# GPU_8_Bit_Logic_Template.net
KiCad netlist of a schematic drawn in EAGLE
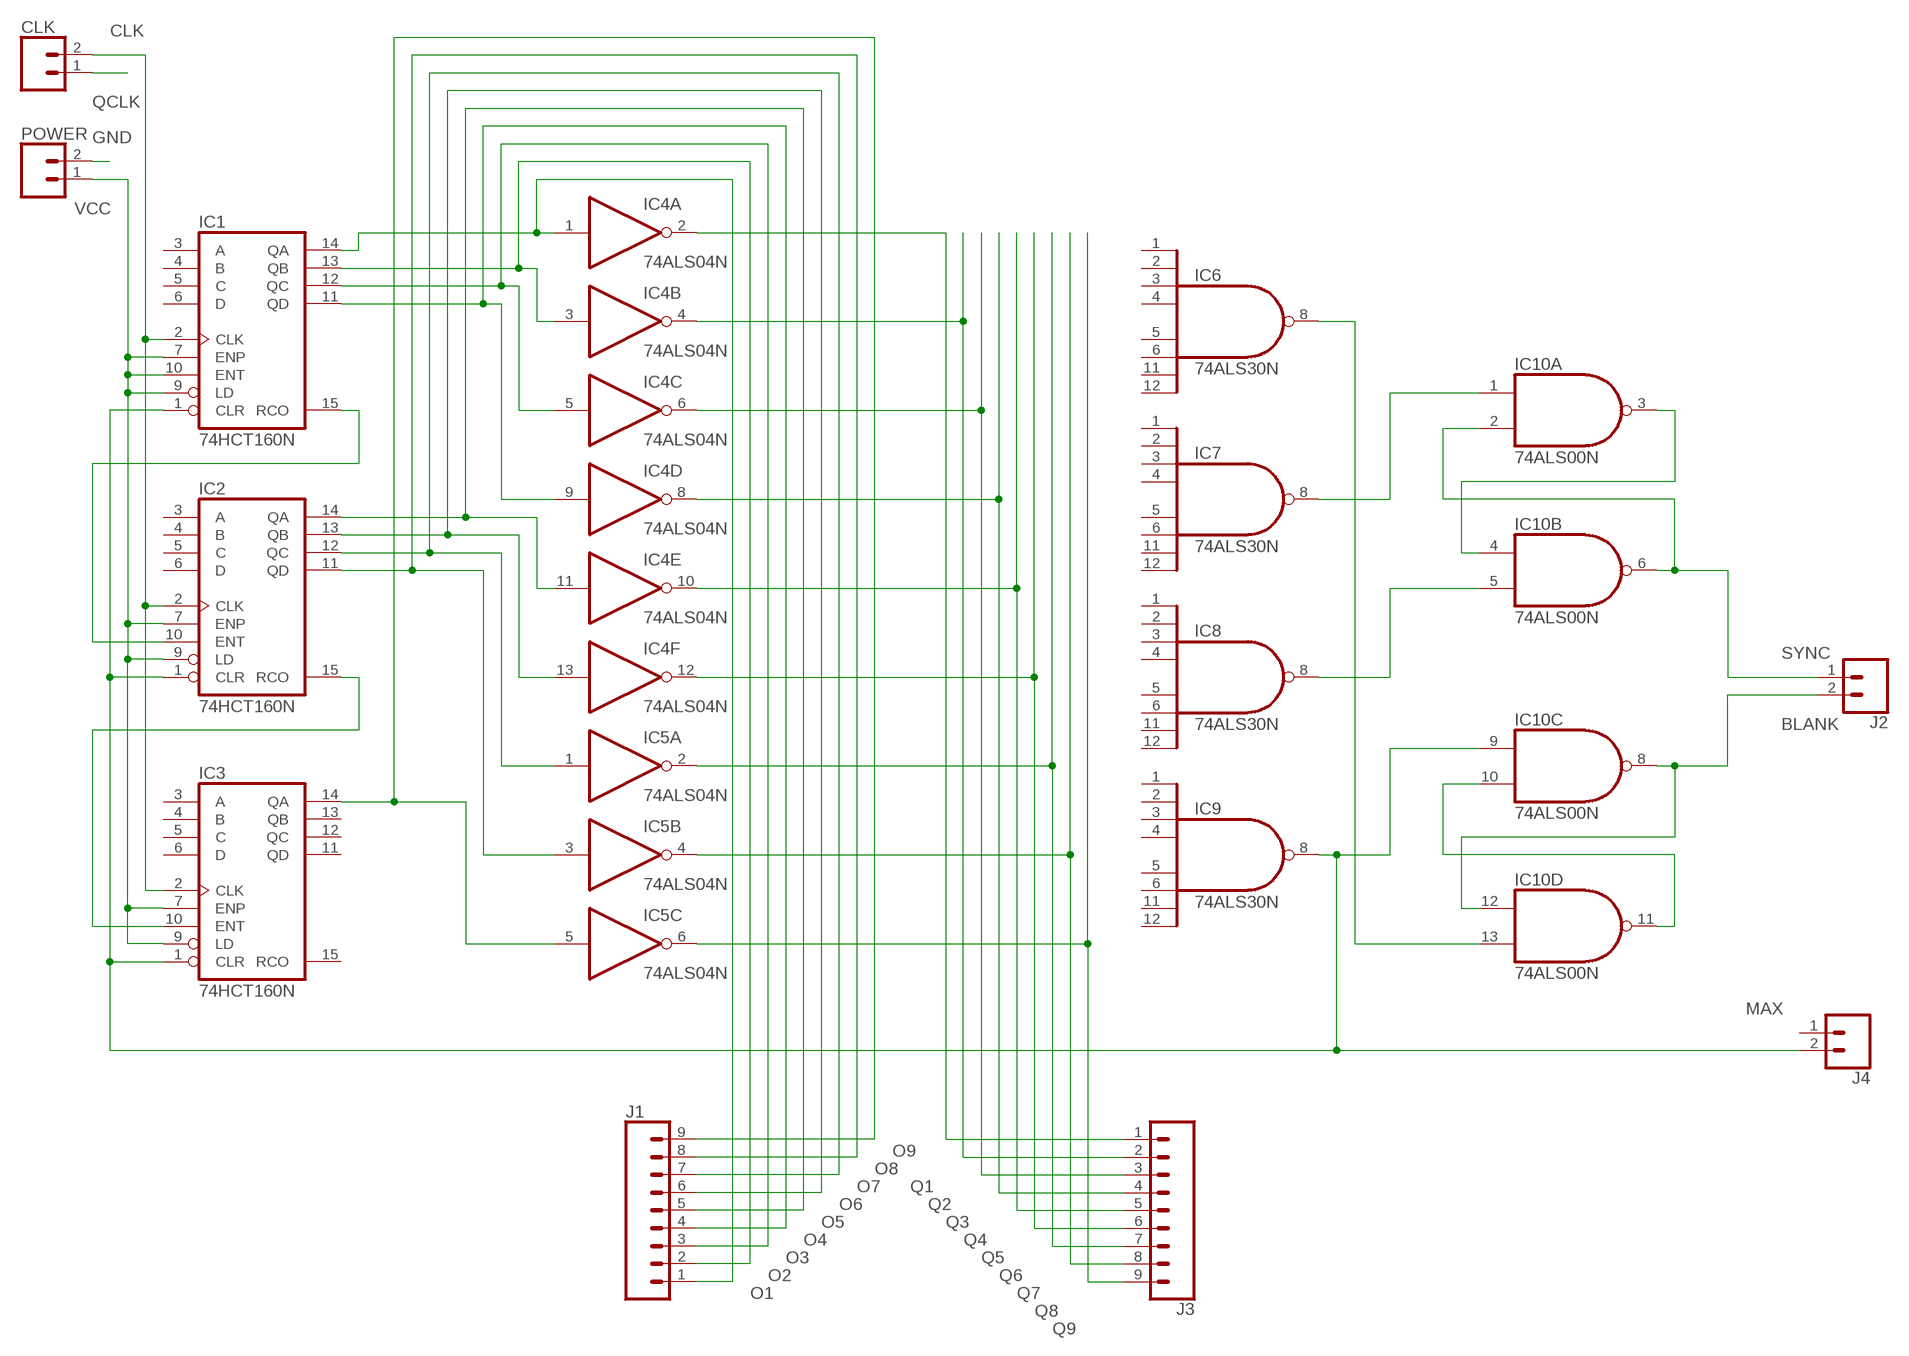
[diagram p0: schematic, sheet 1]

(export (version "E")
  (design (tool "Eeschema 10.0.6"))
  (components
    (comp (ref "CLK")
      (value "CONN_02POGO_PIN_HOLES_ONLY")
      (footprint "eagle-import:1X02_PP_HOLES_ONLY")
      (libsource (lib "eagle-import") (part "CONN_02POGO_PIN_HOLES_ONLY"))
    )
    (comp (ref "IC1")
      (value "74HCT160N")
      (footprint "eagle-import:DIL16")
      (libsource (lib "eagle-import") (part "74160NHCT"))
    )
    (comp (ref "IC2")
      (value "74HCT160N")
      (footprint "eagle-import:DIL16")
      (libsource (lib "eagle-import") (part "74160NHCT"))
    )
    (comp (ref "IC3")
      (value "74HCT160N")
      (footprint "eagle-import:DIL16")
      (libsource (lib "eagle-import") (part "74160NHCT"))
    )
    (comp (ref "IC4")
      (value "74ALS04N")
      (footprint "eagle-import:DIL14")
      (libsource (lib "eagle-import") (part "7404NALS"))
    )
    (comp (ref "IC5")
      (value "74ALS04N")
      (footprint "eagle-import:DIL14")
      (libsource (lib "eagle-import") (part "7404NALS"))
    )
    (comp (ref "IC6")
      (value "74ALS30N")
      (footprint "eagle-import:DIL14")
      (libsource (lib "eagle-import") (part "7430NALS"))
    )
    (comp (ref "IC7")
      (value "74ALS30N")
      (footprint "eagle-import:DIL14")
      (libsource (lib "eagle-import") (part "7430NALS"))
    )
    (comp (ref "IC8")
      (value "74ALS30N")
      (footprint "eagle-import:DIL14")
      (libsource (lib "eagle-import") (part "7430NALS"))
    )
    (comp (ref "IC9")
      (value "74ALS30N")
      (footprint "eagle-import:DIL14")
      (libsource (lib "eagle-import") (part "7430NALS"))
    )
    (comp (ref "IC10")
      (value "74ALS00N")
      (footprint "eagle-import:DIL14")
      (libsource (lib "eagle-import") (part "7400NALS"))
    )
    (comp (ref "J1")
      (value "CONN_09")
      (footprint "eagle-import:1X09")
      (libsource (lib "eagle-import") (part "CONN_09"))
    )
    (comp (ref "J2")
      (value "CONN_02POGO_PIN_HOLES_ONLY")
      (footprint "eagle-import:1X02_PP_HOLES_ONLY")
      (libsource (lib "eagle-import") (part "CONN_02POGO_PIN_HOLES_ONLY"))
    )
    (comp (ref "J3")
      (value "CONN_09")
      (footprint "eagle-import:1X09")
      (libsource (lib "eagle-import") (part "CONN_09"))
    )
    (comp (ref "J4")
      (value "CONN_02POGO_PIN_HOLES_ONLY")
      (footprint "eagle-import:1X02_PP_HOLES_ONLY")
      (libsource (lib "eagle-import") (part "CONN_02POGO_PIN_HOLES_ONLY"))
    )
    (comp (ref "POWER")
      (value "CONN_02POGO_PIN_HOLES_ONLY")
      (footprint "eagle-import:1X02_PP_HOLES_ONLY")
      (libsource (lib "eagle-import") (part "CONN_02POGO_PIN_HOLES_ONLY"))
    )
  )
  (nets
    (net (code "1") (name "/BLANK") (class "Default")
      (node (ref "IC10") (pin "12") (pinfunction "I0_12") (pintype "input"))
      (node (ref "IC10") (pin "8") (pinfunction "O_8") (pintype "output"))
      (node (ref "J2") (pin "2") (pinfunction "2_2") (pintype "passive"))
    )
    (net (code "2") (name "/CLK") (class "Default")
      (node (ref "CLK") (pin "2") (pinfunction "2_2") (pintype "passive"))
      (node (ref "IC1") (pin "2") (pinfunction "CLK_2") (pintype "input"))
      (node (ref "IC2") (pin "2") (pinfunction "CLK_2") (pintype "input"))
      (node (ref "IC3") (pin "2") (pinfunction "CLK_2") (pintype "input"))
    )
    (net (code "3") (name "/GND") (class "Default")
      (node (ref "POWER") (pin "2") (pinfunction "2_2") (pintype "passive"))
    )
    (net (code "4") (name "/MAX") (class "Default")
      (node (ref "IC1") (pin "1") (pinfunction "CLR_1") (pintype "input"))
      (node (ref "IC10") (pin "9") (pinfunction "I0_9") (pintype "input"))
      (node (ref "IC2") (pin "1") (pinfunction "CLR_1") (pintype "input"))
      (node (ref "IC3") (pin "1") (pinfunction "CLR_1") (pintype "input"))
      (node (ref "IC9") (pin "8") (pinfunction "O_8") (pintype "output"))
      (node (ref "J4") (pin "2") (pinfunction "2_2") (pintype "passive"))
    )
    (net (code "5") (name "/O1") (class "Default")
      (node (ref "IC1") (pin "14") (pinfunction "QA_14") (pintype "output"))
      (node (ref "IC4") (pin "1") (pinfunction "I_1") (pintype "input"))
      (node (ref "J1") (pin "1") (pinfunction "1_1") (pintype "passive"))
    )
    (net (code "6") (name "/O2") (class "Default")
      (node (ref "IC1") (pin "13") (pinfunction "QB_13") (pintype "output"))
      (node (ref "IC4") (pin "3") (pinfunction "I_3") (pintype "input"))
      (node (ref "J1") (pin "2") (pinfunction "2_2") (pintype "passive"))
    )
    (net (code "7") (name "/O3") (class "Default")
      (node (ref "IC1") (pin "12") (pinfunction "QC_12") (pintype "output"))
      (node (ref "IC4") (pin "5") (pinfunction "I_5") (pintype "input"))
      (node (ref "J1") (pin "3") (pinfunction "3_3") (pintype "passive"))
    )
    (net (code "8") (name "/O4") (class "Default")
      (node (ref "IC1") (pin "11") (pinfunction "QD_11") (pintype "output"))
      (node (ref "IC4") (pin "9") (pinfunction "I_9") (pintype "input"))
      (node (ref "J1") (pin "4") (pinfunction "4_4") (pintype "passive"))
    )
    (net (code "9") (name "/O5") (class "Default")
      (node (ref "IC2") (pin "14") (pinfunction "QA_14") (pintype "output"))
      (node (ref "IC4") (pin "11") (pinfunction "I_11") (pintype "input"))
      (node (ref "J1") (pin "5") (pinfunction "5_5") (pintype "passive"))
    )
    (net (code "10") (name "/O6") (class "Default")
      (node (ref "IC2") (pin "13") (pinfunction "QB_13") (pintype "output"))
      (node (ref "IC4") (pin "13") (pinfunction "I_13") (pintype "input"))
      (node (ref "J1") (pin "6") (pinfunction "6_6") (pintype "passive"))
    )
    (net (code "11") (name "/O7") (class "Default")
      (node (ref "IC2") (pin "12") (pinfunction "QC_12") (pintype "output"))
      (node (ref "IC5") (pin "1") (pinfunction "I_1") (pintype "input"))
      (node (ref "J1") (pin "7") (pinfunction "7_7") (pintype "passive"))
    )
    (net (code "12") (name "/O8") (class "Default")
      (node (ref "IC2") (pin "11") (pinfunction "QD_11") (pintype "output"))
      (node (ref "IC5") (pin "3") (pinfunction "I_3") (pintype "input"))
      (node (ref "J1") (pin "8") (pinfunction "8_8") (pintype "passive"))
    )
    (net (code "13") (name "/O9") (class "Default")
      (node (ref "IC3") (pin "14") (pinfunction "QA_14") (pintype "output"))
      (node (ref "IC5") (pin "5") (pinfunction "I_5") (pintype "input"))
      (node (ref "J1") (pin "9") (pinfunction "9_9") (pintype "passive"))
    )
    (net (code "14") (name "/Q1") (class "Default")
      (node (ref "IC4") (pin "2") (pinfunction "O_2") (pintype "output"))
      (node (ref "J3") (pin "1") (pinfunction "1_1") (pintype "passive"))
    )
    (net (code "15") (name "/Q2") (class "Default")
      (node (ref "IC4") (pin "4") (pinfunction "O_4") (pintype "output"))
      (node (ref "J3") (pin "2") (pinfunction "2_2") (pintype "passive"))
    )
    (net (code "16") (name "/Q3") (class "Default")
      (node (ref "IC4") (pin "6") (pinfunction "O_6") (pintype "output"))
      (node (ref "J3") (pin "3") (pinfunction "3_3") (pintype "passive"))
    )
    (net (code "17") (name "/Q4") (class "Default")
      (node (ref "IC4") (pin "8") (pinfunction "O_8") (pintype "output"))
      (node (ref "J3") (pin "4") (pinfunction "4_4") (pintype "passive"))
    )
    (net (code "18") (name "/Q5") (class "Default")
      (node (ref "IC4") (pin "10") (pinfunction "O_10") (pintype "output"))
      (node (ref "J3") (pin "5") (pinfunction "5_5") (pintype "passive"))
    )
    (net (code "19") (name "/Q6") (class "Default")
      (node (ref "IC4") (pin "12") (pinfunction "O_12") (pintype "output"))
      (node (ref "J3") (pin "6") (pinfunction "6_6") (pintype "passive"))
    )
    (net (code "20") (name "/Q7") (class "Default")
      (node (ref "IC5") (pin "2") (pinfunction "O_2") (pintype "output"))
      (node (ref "J3") (pin "7") (pinfunction "7_7") (pintype "passive"))
    )
    (net (code "21") (name "/Q8") (class "Default")
      (node (ref "IC5") (pin "4") (pinfunction "O_4") (pintype "output"))
      (node (ref "J3") (pin "8") (pinfunction "8_8") (pintype "passive"))
    )
    (net (code "22") (name "/Q9") (class "Default")
      (node (ref "IC5") (pin "6") (pinfunction "O_6") (pintype "output"))
      (node (ref "J3") (pin "9") (pinfunction "9_9") (pintype "passive"))
    )
    (net (code "23") (name "/QCLK") (class "Default")
      (node (ref "CLK") (pin "1") (pinfunction "1_1") (pintype "passive"))
    )
    (net (code "24") (name "/SYNC") (class "Default")
      (node (ref "IC10") (pin "2") (pinfunction "I1_2") (pintype "input"))
      (node (ref "IC10") (pin "6") (pinfunction "O_6") (pintype "output"))
      (node (ref "J2") (pin "1") (pinfunction "1_1") (pintype "passive"))
    )
    (net (code "25") (name "/VCC") (class "Default")
      (node (ref "IC1") (pin "10") (pinfunction "ENT_10") (pintype "input"))
      (node (ref "IC1") (pin "7") (pinfunction "ENP_7") (pintype "input"))
      (node (ref "IC1") (pin "9") (pinfunction "LD_9") (pintype "input"))
      (node (ref "IC2") (pin "7") (pinfunction "ENP_7") (pintype "input"))
      (node (ref "IC2") (pin "9") (pinfunction "LD_9") (pintype "input"))
      (node (ref "IC3") (pin "7") (pinfunction "ENP_7") (pintype "input"))
      (node (ref "IC3") (pin "9") (pinfunction "LD_9") (pintype "input"))
      (node (ref "POWER") (pin "1") (pinfunction "1_1") (pintype "passive"))
    )
    (net (code "26") (name "Net-(IC1A-RCO)") (class "Default")
      (node (ref "IC1") (pin "15") (pinfunction "RCO_15") (pintype "output"))
      (node (ref "IC2") (pin "10") (pinfunction "ENT_10") (pintype "input"))
    )
    (net (code "27") (name "Net-(IC2A-RCO)") (class "Default")
      (node (ref "IC2") (pin "15") (pinfunction "RCO_15") (pintype "output"))
      (node (ref "IC3") (pin "10") (pinfunction "ENT_10") (pintype "input"))
    )
    (net (code "28") (name "Net-(IC10A-I0)") (class "Default")
      (node (ref "IC10") (pin "1") (pinfunction "I0_1") (pintype "input"))
      (node (ref "IC7") (pin "8") (pinfunction "O_8") (pintype "output"))
    )
    (net (code "29") (name "Net-(IC10A-O)") (class "Default")
      (node (ref "IC10") (pin "3") (pinfunction "O_3") (pintype "output"))
      (node (ref "IC10") (pin "4") (pinfunction "I0_4") (pintype "input"))
    )
    (net (code "30") (name "Net-(IC10B-I1)") (class "Default")
      (node (ref "IC10") (pin "5") (pinfunction "I1_5") (pintype "input"))
      (node (ref "IC8") (pin "8") (pinfunction "O_8") (pintype "output"))
    )
    (net (code "31") (name "Net-(IC10C-I1)") (class "Default")
      (node (ref "IC10") (pin "10") (pinfunction "I1_10") (pintype "input"))
      (node (ref "IC10") (pin "11") (pinfunction "O_11") (pintype "output"))
    )
    (net (code "32") (name "Net-(IC10D-I1)") (class "Default")
      (node (ref "IC10") (pin "13") (pinfunction "I1_13") (pintype "input"))
      (node (ref "IC6") (pin "8") (pinfunction "O_8") (pintype "output"))
    )
    (net (code "33") (name "unconnected-(IC1A-A-Pad3)") (class "Default")
      (node (ref "IC1") (pin "3") (pinfunction "A_3") (pintype "input"))
    )
    (net (code "34") (name "unconnected-(IC1A-B-Pad4)") (class "Default")
      (node (ref "IC1") (pin "4") (pinfunction "B_4") (pintype "input"))
    )
    (net (code "35") (name "unconnected-(IC1A-C-Pad5)") (class "Default")
      (node (ref "IC1") (pin "5") (pinfunction "C_5") (pintype "input"))
    )
    (net (code "36") (name "unconnected-(IC1A-D-Pad6)") (class "Default")
      (node (ref "IC1") (pin "6") (pinfunction "D_6") (pintype "input"))
    )
    (net (code "37") (name "unconnected-(IC2A-A-Pad3)") (class "Default")
      (node (ref "IC2") (pin "3") (pinfunction "A_3") (pintype "input"))
    )
    (net (code "38") (name "unconnected-(IC2A-B-Pad4)") (class "Default")
      (node (ref "IC2") (pin "4") (pinfunction "B_4") (pintype "input"))
    )
    (net (code "39") (name "unconnected-(IC2A-C-Pad5)") (class "Default")
      (node (ref "IC2") (pin "5") (pinfunction "C_5") (pintype "input"))
    )
    (net (code "40") (name "unconnected-(IC2A-D-Pad6)") (class "Default")
      (node (ref "IC2") (pin "6") (pinfunction "D_6") (pintype "input"))
    )
    (net (code "41") (name "unconnected-(IC3A-A-Pad3)") (class "Default")
      (node (ref "IC3") (pin "3") (pinfunction "A_3") (pintype "input"))
    )
    (net (code "42") (name "unconnected-(IC3A-B-Pad4)") (class "Default")
      (node (ref "IC3") (pin "4") (pinfunction "B_4") (pintype "input"))
    )
    (net (code "43") (name "unconnected-(IC3A-C-Pad5)") (class "Default")
      (node (ref "IC3") (pin "5") (pinfunction "C_5") (pintype "input"))
    )
    (net (code "44") (name "unconnected-(IC3A-D-Pad6)") (class "Default")
      (node (ref "IC3") (pin "6") (pinfunction "D_6") (pintype "input"))
    )
    (net (code "45") (name "unconnected-(IC3A-QB-Pad13)") (class "Default")
      (node (ref "IC3") (pin "13") (pinfunction "QB_13") (pintype "output"))
    )
    (net (code "46") (name "unconnected-(IC3A-QC-Pad12)") (class "Default")
      (node (ref "IC3") (pin "12") (pinfunction "QC_12") (pintype "output"))
    )
    (net (code "47") (name "unconnected-(IC3A-QD-Pad11)") (class "Default")
      (node (ref "IC3") (pin "11") (pinfunction "QD_11") (pintype "output"))
    )
    (net (code "48") (name "unconnected-(IC3A-RCO-Pad15)") (class "Default")
      (node (ref "IC3") (pin "15") (pinfunction "RCO_15") (pintype "output"))
    )
    (net (code "49") (name "unconnected-(IC6A-I0-Pad1)") (class "Default")
      (node (ref "IC6") (pin "1") (pinfunction "I0_1") (pintype "input"))
    )
    (net (code "50") (name "unconnected-(IC6A-I1-Pad2)") (class "Default")
      (node (ref "IC6") (pin "2") (pinfunction "I1_2") (pintype "input"))
    )
    (net (code "51") (name "unconnected-(IC6A-I2-Pad3)") (class "Default")
      (node (ref "IC6") (pin "3") (pinfunction "I2_3") (pintype "input"))
    )
    (net (code "52") (name "unconnected-(IC6A-I3-Pad4)") (class "Default")
      (node (ref "IC6") (pin "4") (pinfunction "I3_4") (pintype "input"))
    )
    (net (code "53") (name "unconnected-(IC6A-I4-Pad5)") (class "Default")
      (node (ref "IC6") (pin "5") (pinfunction "I4_5") (pintype "input"))
    )
    (net (code "54") (name "unconnected-(IC6A-I5-Pad6)") (class "Default")
      (node (ref "IC6") (pin "6") (pinfunction "I5_6") (pintype "input"))
    )
    (net (code "55") (name "unconnected-(IC6A-I6-Pad11)") (class "Default")
      (node (ref "IC6") (pin "11") (pinfunction "I6_11") (pintype "input"))
    )
    (net (code "56") (name "unconnected-(IC6A-I7-Pad12)") (class "Default")
      (node (ref "IC6") (pin "12") (pinfunction "I7_12") (pintype "input"))
    )
    (net (code "57") (name "unconnected-(IC7A-I0-Pad1)") (class "Default")
      (node (ref "IC7") (pin "1") (pinfunction "I0_1") (pintype "input"))
    )
    (net (code "58") (name "unconnected-(IC7A-I1-Pad2)") (class "Default")
      (node (ref "IC7") (pin "2") (pinfunction "I1_2") (pintype "input"))
    )
    (net (code "59") (name "unconnected-(IC7A-I2-Pad3)") (class "Default")
      (node (ref "IC7") (pin "3") (pinfunction "I2_3") (pintype "input"))
    )
    (net (code "60") (name "unconnected-(IC7A-I3-Pad4)") (class "Default")
      (node (ref "IC7") (pin "4") (pinfunction "I3_4") (pintype "input"))
    )
    (net (code "61") (name "unconnected-(IC7A-I4-Pad5)") (class "Default")
      (node (ref "IC7") (pin "5") (pinfunction "I4_5") (pintype "input"))
    )
    (net (code "62") (name "unconnected-(IC7A-I5-Pad6)") (class "Default")
      (node (ref "IC7") (pin "6") (pinfunction "I5_6") (pintype "input"))
    )
    (net (code "63") (name "unconnected-(IC7A-I6-Pad11)") (class "Default")
      (node (ref "IC7") (pin "11") (pinfunction "I6_11") (pintype "input"))
    )
    (net (code "64") (name "unconnected-(IC7A-I7-Pad12)") (class "Default")
      (node (ref "IC7") (pin "12") (pinfunction "I7_12") (pintype "input"))
    )
    (net (code "65") (name "unconnected-(IC8A-I0-Pad1)") (class "Default")
      (node (ref "IC8") (pin "1") (pinfunction "I0_1") (pintype "input"))
    )
    (net (code "66") (name "unconnected-(IC8A-I1-Pad2)") (class "Default")
      (node (ref "IC8") (pin "2") (pinfunction "I1_2") (pintype "input"))
    )
    (net (code "67") (name "unconnected-(IC8A-I2-Pad3)") (class "Default")
      (node (ref "IC8") (pin "3") (pinfunction "I2_3") (pintype "input"))
    )
    (net (code "68") (name "unconnected-(IC8A-I3-Pad4)") (class "Default")
      (node (ref "IC8") (pin "4") (pinfunction "I3_4") (pintype "input"))
    )
    (net (code "69") (name "unconnected-(IC8A-I4-Pad5)") (class "Default")
      (node (ref "IC8") (pin "5") (pinfunction "I4_5") (pintype "input"))
    )
    (net (code "70") (name "unconnected-(IC8A-I5-Pad6)") (class "Default")
      (node (ref "IC8") (pin "6") (pinfunction "I5_6") (pintype "input"))
    )
    (net (code "71") (name "unconnected-(IC8A-I6-Pad11)") (class "Default")
      (node (ref "IC8") (pin "11") (pinfunction "I6_11") (pintype "input"))
    )
    (net (code "72") (name "unconnected-(IC8A-I7-Pad12)") (class "Default")
      (node (ref "IC8") (pin "12") (pinfunction "I7_12") (pintype "input"))
    )
    (net (code "73") (name "unconnected-(IC9A-I0-Pad1)") (class "Default")
      (node (ref "IC9") (pin "1") (pinfunction "I0_1") (pintype "input"))
    )
    (net (code "74") (name "unconnected-(IC9A-I1-Pad2)") (class "Default")
      (node (ref "IC9") (pin "2") (pinfunction "I1_2") (pintype "input"))
    )
    (net (code "75") (name "unconnected-(IC9A-I2-Pad3)") (class "Default")
      (node (ref "IC9") (pin "3") (pinfunction "I2_3") (pintype "input"))
    )
    (net (code "76") (name "unconnected-(IC9A-I3-Pad4)") (class "Default")
      (node (ref "IC9") (pin "4") (pinfunction "I3_4") (pintype "input"))
    )
    (net (code "77") (name "unconnected-(IC9A-I4-Pad5)") (class "Default")
      (node (ref "IC9") (pin "5") (pinfunction "I4_5") (pintype "input"))
    )
    (net (code "78") (name "unconnected-(IC9A-I5-Pad6)") (class "Default")
      (node (ref "IC9") (pin "6") (pinfunction "I5_6") (pintype "input"))
    )
    (net (code "79") (name "unconnected-(IC9A-I6-Pad11)") (class "Default")
      (node (ref "IC9") (pin "11") (pinfunction "I6_11") (pintype "input"))
    )
    (net (code "80") (name "unconnected-(IC9A-I7-Pad12)") (class "Default")
      (node (ref "IC9") (pin "12") (pinfunction "I7_12") (pintype "input"))
    )
    (net (code "81") (name "unconnected-(J4-Pad1)") (class "Default")
      (node (ref "J4") (pin "1") (pinfunction "1_1") (pintype "passive"))
    )
  )
)
